# matrix5x5.net
KiCad netlist of a schematic drawn in EAGLE
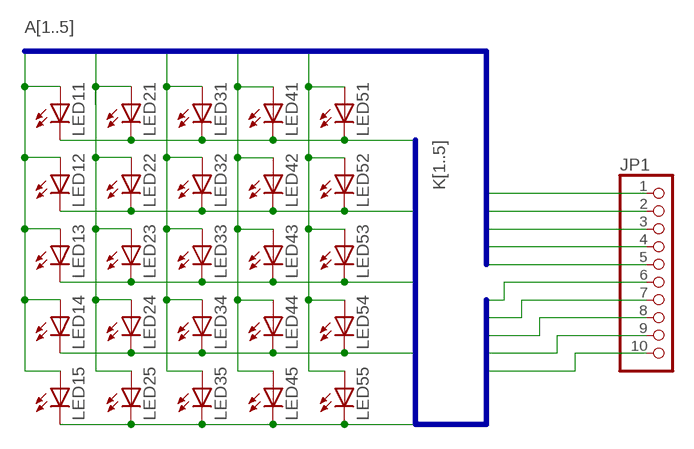
[diagram p0: schematic, sheet 1]

(export (version "E")
  (design (tool "Eeschema 10.0.6"))
  (components
    (comp (ref "JP1")
      (value "PINHD-1X10")
      (footprint "eagle-import:1X10")
      (libsource (lib "eagle-import") (part "PINHD-1X10"))
    )
    (comp (ref "LED11")
      (value "LED5MM")
      (footprint "eagle-import:LED5MM")
      (libsource (lib "eagle-import") (part "LED5MM"))
    )
    (comp (ref "LED12")
      (value "LED5MM")
      (footprint "eagle-import:LED5MM")
      (libsource (lib "eagle-import") (part "LED5MM"))
    )
    (comp (ref "LED13")
      (value "LED5MM")
      (footprint "eagle-import:LED5MM")
      (libsource (lib "eagle-import") (part "LED5MM"))
    )
    (comp (ref "LED14")
      (value "LED5MM")
      (footprint "eagle-import:LED5MM")
      (libsource (lib "eagle-import") (part "LED5MM"))
    )
    (comp (ref "LED15")
      (value "LED5MM")
      (footprint "eagle-import:LED5MM")
      (libsource (lib "eagle-import") (part "LED5MM"))
    )
    (comp (ref "LED21")
      (value "LED5MM")
      (footprint "eagle-import:LED5MM")
      (libsource (lib "eagle-import") (part "LED5MM"))
    )
    (comp (ref "LED22")
      (value "LED5MM")
      (footprint "eagle-import:LED5MM")
      (libsource (lib "eagle-import") (part "LED5MM"))
    )
    (comp (ref "LED23")
      (value "LED5MM")
      (footprint "eagle-import:LED5MM")
      (libsource (lib "eagle-import") (part "LED5MM"))
    )
    (comp (ref "LED24")
      (value "LED5MM")
      (footprint "eagle-import:LED5MM")
      (libsource (lib "eagle-import") (part "LED5MM"))
    )
    (comp (ref "LED25")
      (value "LED5MM")
      (footprint "eagle-import:LED5MM")
      (libsource (lib "eagle-import") (part "LED5MM"))
    )
    (comp (ref "LED31")
      (value "LED5MM")
      (footprint "eagle-import:LED5MM")
      (libsource (lib "eagle-import") (part "LED5MM"))
    )
    (comp (ref "LED32")
      (value "LED5MM")
      (footprint "eagle-import:LED5MM")
      (libsource (lib "eagle-import") (part "LED5MM"))
    )
    (comp (ref "LED33")
      (value "LED5MM")
      (footprint "eagle-import:LED5MM")
      (libsource (lib "eagle-import") (part "LED5MM"))
    )
    (comp (ref "LED34")
      (value "LED5MM")
      (footprint "eagle-import:LED5MM")
      (libsource (lib "eagle-import") (part "LED5MM"))
    )
    (comp (ref "LED35")
      (value "LED5MM")
      (footprint "eagle-import:LED5MM")
      (libsource (lib "eagle-import") (part "LED5MM"))
    )
    (comp (ref "LED41")
      (value "LED5MM")
      (footprint "eagle-import:LED5MM")
      (libsource (lib "eagle-import") (part "LED5MM"))
    )
    (comp (ref "LED42")
      (value "LED5MM")
      (footprint "eagle-import:LED5MM")
      (libsource (lib "eagle-import") (part "LED5MM"))
    )
    (comp (ref "LED43")
      (value "LED5MM")
      (footprint "eagle-import:LED5MM")
      (libsource (lib "eagle-import") (part "LED5MM"))
    )
    (comp (ref "LED44")
      (value "LED5MM")
      (footprint "eagle-import:LED5MM")
      (libsource (lib "eagle-import") (part "LED5MM"))
    )
    (comp (ref "LED45")
      (value "LED5MM")
      (footprint "eagle-import:LED5MM")
      (libsource (lib "eagle-import") (part "LED5MM"))
    )
    (comp (ref "LED51")
      (value "LED5MM")
      (footprint "eagle-import:LED5MM")
      (libsource (lib "eagle-import") (part "LED5MM"))
    )
    (comp (ref "LED52")
      (value "LED5MM")
      (footprint "eagle-import:LED5MM")
      (libsource (lib "eagle-import") (part "LED5MM"))
    )
    (comp (ref "LED53")
      (value "LED5MM")
      (footprint "eagle-import:LED5MM")
      (libsource (lib "eagle-import") (part "LED5MM"))
    )
    (comp (ref "LED54")
      (value "LED5MM")
      (footprint "eagle-import:LED5MM")
      (libsource (lib "eagle-import") (part "LED5MM"))
    )
    (comp (ref "LED55")
      (value "LED5MM")
      (footprint "eagle-import:LED5MM")
      (libsource (lib "eagle-import") (part "LED5MM"))
    )
  )
  (nets
    (net (code "1") (name "/A1") (class "Default")
      (node (ref "JP1") (pin "1") (pinfunction "1_1") (pintype "passive"))
      (node (ref "LED11") (pin "A") (pinfunction "A_A") (pintype "passive"))
      (node (ref "LED12") (pin "A") (pinfunction "A_A") (pintype "passive"))
      (node (ref "LED13") (pin "A") (pinfunction "A_A") (pintype "passive"))
      (node (ref "LED14") (pin "A") (pinfunction "A_A") (pintype "passive"))
      (node (ref "LED15") (pin "A") (pinfunction "A_A") (pintype "passive"))
    )
    (net (code "2") (name "/A2") (class "Default")
      (node (ref "JP1") (pin "2") (pinfunction "2_2") (pintype "passive"))
      (node (ref "LED21") (pin "A") (pinfunction "A_A") (pintype "passive"))
      (node (ref "LED22") (pin "A") (pinfunction "A_A") (pintype "passive"))
      (node (ref "LED23") (pin "A") (pinfunction "A_A") (pintype "passive"))
      (node (ref "LED24") (pin "A") (pinfunction "A_A") (pintype "passive"))
      (node (ref "LED25") (pin "A") (pinfunction "A_A") (pintype "passive"))
    )
    (net (code "3") (name "/A3") (class "Default")
      (node (ref "JP1") (pin "3") (pinfunction "3_3") (pintype "passive"))
      (node (ref "LED31") (pin "A") (pinfunction "A_A") (pintype "passive"))
      (node (ref "LED32") (pin "A") (pinfunction "A_A") (pintype "passive"))
      (node (ref "LED33") (pin "A") (pinfunction "A_A") (pintype "passive"))
      (node (ref "LED34") (pin "A") (pinfunction "A_A") (pintype "passive"))
      (node (ref "LED35") (pin "A") (pinfunction "A_A") (pintype "passive"))
    )
    (net (code "4") (name "/A4") (class "Default")
      (node (ref "JP1") (pin "4") (pinfunction "4_4") (pintype "passive"))
      (node (ref "LED41") (pin "A") (pinfunction "A_A") (pintype "passive"))
      (node (ref "LED42") (pin "A") (pinfunction "A_A") (pintype "passive"))
      (node (ref "LED43") (pin "A") (pinfunction "A_A") (pintype "passive"))
      (node (ref "LED44") (pin "A") (pinfunction "A_A") (pintype "passive"))
      (node (ref "LED45") (pin "A") (pinfunction "A_A") (pintype "passive"))
    )
    (net (code "5") (name "/A5") (class "Default")
      (node (ref "JP1") (pin "5") (pinfunction "5_5") (pintype "passive"))
      (node (ref "LED51") (pin "A") (pinfunction "A_A") (pintype "passive"))
      (node (ref "LED52") (pin "A") (pinfunction "A_A") (pintype "passive"))
      (node (ref "LED53") (pin "A") (pinfunction "A_A") (pintype "passive"))
      (node (ref "LED54") (pin "A") (pinfunction "A_A") (pintype "passive"))
      (node (ref "LED55") (pin "A") (pinfunction "A_A") (pintype "passive"))
    )
    (net (code "7") (name "/K1") (class "Default")
      (node (ref "JP1") (pin "6") (pinfunction "6_6") (pintype "passive"))
      (node (ref "LED11") (pin "K") (pinfunction "C_K") (pintype "passive"))
      (node (ref "LED21") (pin "K") (pinfunction "C_K") (pintype "passive"))
      (node (ref "LED31") (pin "K") (pinfunction "C_K") (pintype "passive"))
      (node (ref "LED41") (pin "K") (pinfunction "C_K") (pintype "passive"))
      (node (ref "LED51") (pin "K") (pinfunction "C_K") (pintype "passive"))
    )
    (net (code "8") (name "/K2") (class "Default")
      (node (ref "JP1") (pin "7") (pinfunction "7_7") (pintype "passive"))
      (node (ref "LED12") (pin "K") (pinfunction "C_K") (pintype "passive"))
      (node (ref "LED22") (pin "K") (pinfunction "C_K") (pintype "passive"))
      (node (ref "LED32") (pin "K") (pinfunction "C_K") (pintype "passive"))
      (node (ref "LED42") (pin "K") (pinfunction "C_K") (pintype "passive"))
      (node (ref "LED52") (pin "K") (pinfunction "C_K") (pintype "passive"))
    )
    (net (code "9") (name "/K3") (class "Default")
      (node (ref "JP1") (pin "8") (pinfunction "8_8") (pintype "passive"))
      (node (ref "LED13") (pin "K") (pinfunction "C_K") (pintype "passive"))
      (node (ref "LED23") (pin "K") (pinfunction "C_K") (pintype "passive"))
      (node (ref "LED33") (pin "K") (pinfunction "C_K") (pintype "passive"))
      (node (ref "LED43") (pin "K") (pinfunction "C_K") (pintype "passive"))
      (node (ref "LED53") (pin "K") (pinfunction "C_K") (pintype "passive"))
    )
    (net (code "10") (name "/K4") (class "Default")
      (node (ref "JP1") (pin "9") (pinfunction "9_9") (pintype "passive"))
      (node (ref "LED14") (pin "K") (pinfunction "C_K") (pintype "passive"))
      (node (ref "LED24") (pin "K") (pinfunction "C_K") (pintype "passive"))
      (node (ref "LED34") (pin "K") (pinfunction "C_K") (pintype "passive"))
      (node (ref "LED44") (pin "K") (pinfunction "C_K") (pintype "passive"))
      (node (ref "LED54") (pin "K") (pinfunction "C_K") (pintype "passive"))
    )
    (net (code "11") (name "/K5") (class "Default")
      (node (ref "JP1") (pin "10") (pinfunction "10_10") (pintype "passive"))
      (node (ref "LED15") (pin "K") (pinfunction "C_K") (pintype "passive"))
      (node (ref "LED25") (pin "K") (pinfunction "C_K") (pintype "passive"))
      (node (ref "LED35") (pin "K") (pinfunction "C_K") (pintype "passive"))
      (node (ref "LED45") (pin "K") (pinfunction "C_K") (pintype "passive"))
      (node (ref "LED55") (pin "K") (pinfunction "C_K") (pintype "passive"))
    )
  )
)
